# COUNT.net
KiCad netlist of a schematic drawn in EAGLE
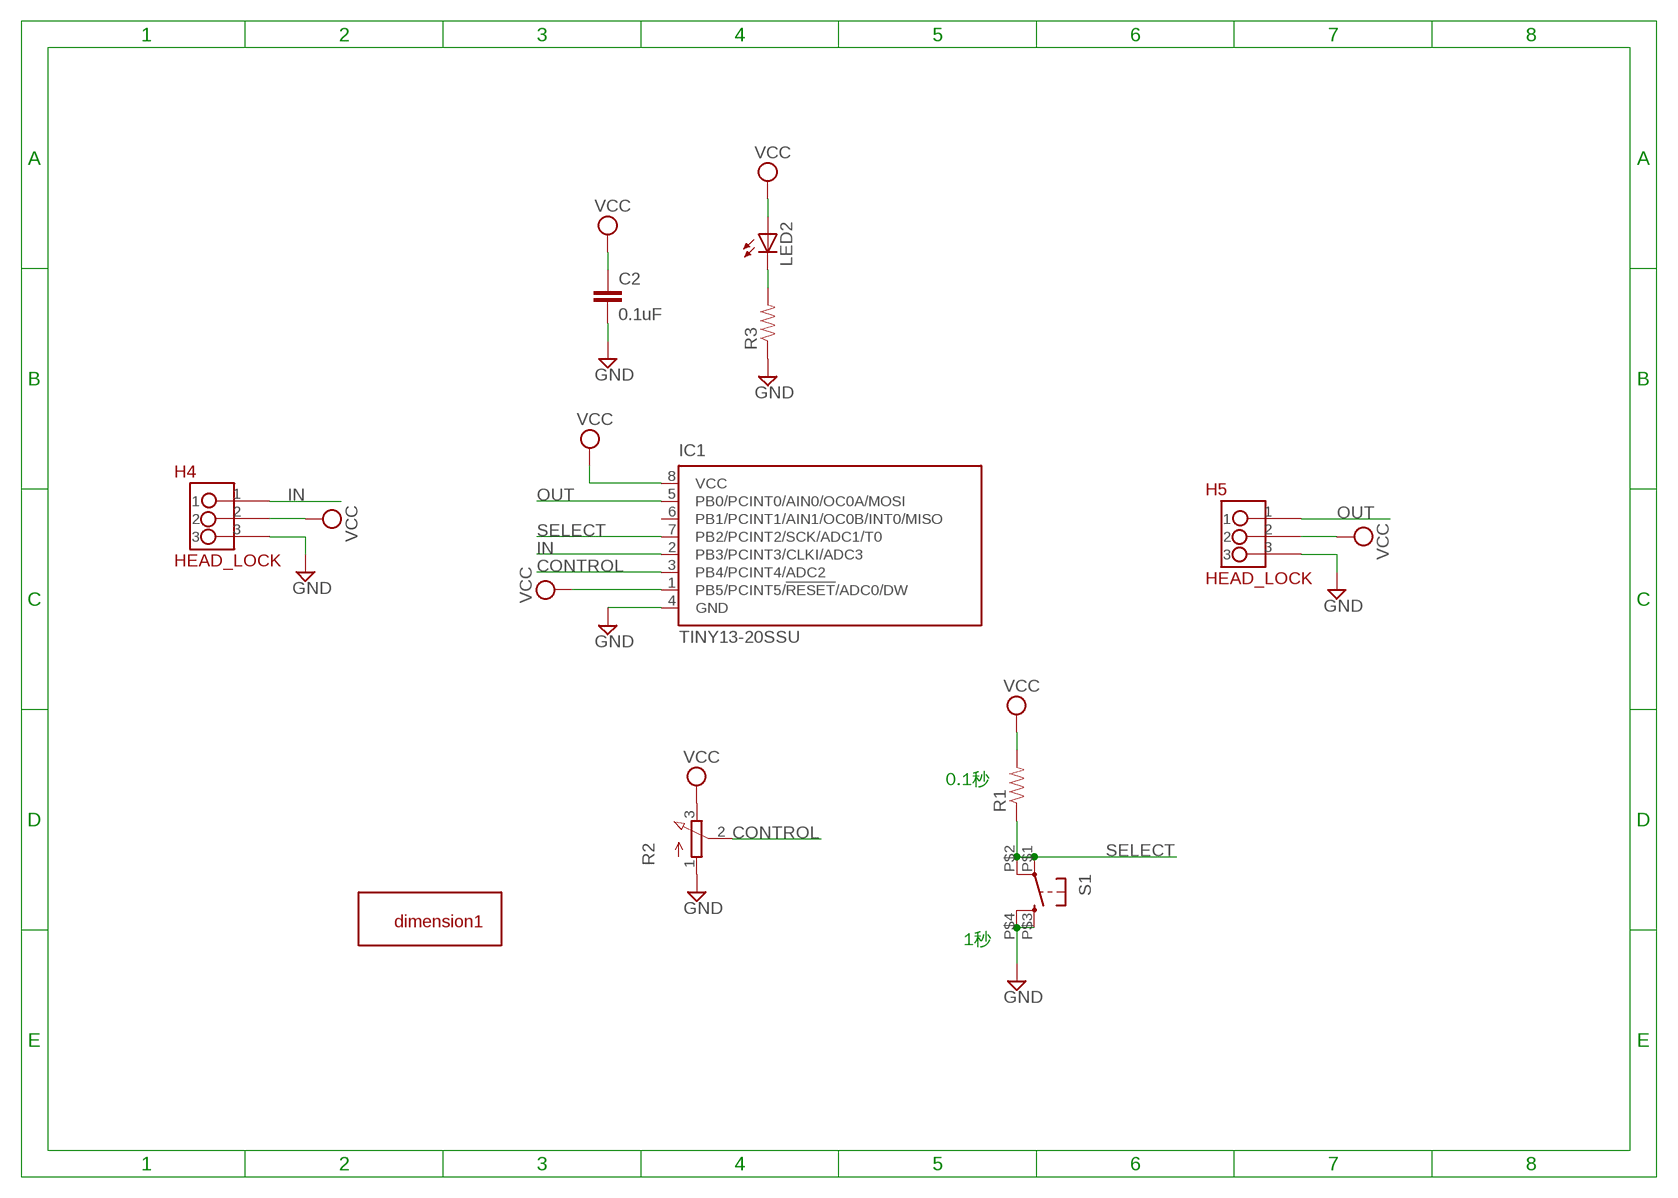
[diagram p0: schematic, sheet 1]

(export (version "E")
  (design (tool "Eeschema 10.0.6"))
  (components
    (comp (ref "C2")
      (value "0.1uF")
      (footprint "eagle-import:0603-CAP")
      (libsource (lib "eagle-import") (part "CAP0603-CAP"))
    )
    (comp (ref "H4")
      (value "HEAD_LOCK")
      (footprint "eagle-import:HEAD_LOCK")
      (libsource (lib "eagle-import") (part "HEAD_LOCK"))
    )
    (comp (ref "H5")
      (value "HEAD_LOCK")
      (footprint "eagle-import:HEAD_LOCK")
      (libsource (lib "eagle-import") (part "HEAD_LOCK"))
    )
    (comp (ref "IC1")
      (value "TINY13-20SSU")
      (footprint "eagle-import:8S1")
      (fields (field (name "MPN") "ATTINY13-20SSU"))
      (libsource (lib "eagle-import") (part "TINY13SSU-20"))
    )
    (comp (ref "LED2")
      (value "LED_ESML0603")
      (footprint "eagle-import:LED_SML0603")
      (libsource (lib "eagle-import") (part "LED_ESML0603"))
    )
    (comp (ref "R1")
      (value "RESISTOR0603-RES")
      (footprint "eagle-import:0603-RES")
      (libsource (lib "eagle-import") (part "RESISTOR0603-RES"))
    )
    (comp (ref "R2")
      (value "3RP/1610N")
      (footprint "eagle-import:3RP_1610N")
      (libsource (lib "eagle-import") (part "3RP/1610N"))
    )
    (comp (ref "R3")
      (value "0.27OHM-1/10W-1%(0603)")
      (footprint "eagle-import:0603-RES")
      (libsource (lib "eagle-import") (part "0.27OHM-1/10W-1%(0603)"))
    )
    (comp (ref "S1")
      (value "TAC_SWITCHKSA_SEALED")
      (footprint "eagle-import:KSA_SEALED_TAC_SWITCH")
      (libsource (lib "eagle-import") (part "TAC_SWITCHKSA_SEALED"))
    )
    (comp (ref "U$1")
      (value "DIMENSION1")
      (footprint "eagle-import:DIMENSION1")
      (libsource (lib "eagle-import") (part "DIMENSION1"))
    )
  )
  (nets
    (net (code "1") (name "/CONTROL") (class "Default")
      (node (ref "IC1") (pin "3") (pinfunction "PB4/PCINT4/ADC2_3") (pintype "bidirectional"))
      (node (ref "R2") (pin "2") (pinfunction "S_2") (pintype "passive"))
    )
    (net (code "2") (name "/IN") (class "Default")
      (node (ref "H4") (pin "1") (pinfunction "1_1") (pintype "passive"))
      (node (ref "IC1") (pin "2") (pinfunction "PB3/PCINT3/CLKI/ADC3_2") (pintype "bidirectional"))
    )
    (net (code "3") (name "/OUT") (class "Default")
      (node (ref "H5") (pin "1") (pinfunction "1_1") (pintype "passive"))
      (node (ref "IC1") (pin "5") (pinfunction "PB0/PCINT0/AIN0/OC0A/MOSI_5") (pintype "bidirectional"))
    )
    (net (code "4") (name "/SELECT") (class "Default")
      (node (ref "IC1") (pin "7") (pinfunction "PB2/PCINT2/SCK/ADC1/T0_7") (pintype "bidirectional"))
      (node (ref "R1") (pin "1") (pinfunction "1_1") (pintype "passive"))
      (node (ref "S1") (pin "P$1") (pinfunction "1_P$1") (pintype "passive"))
      (node (ref "S1") (pin "P$2") (pinfunction "2_P$2") (pintype "passive"))
    )
    (net (code "5") (name "GND") (class "Default")
      (node (ref "C2") (pin "2") (pinfunction "2_2") (pintype "passive"))
      (node (ref "H4") (pin "3") (pinfunction "3_3") (pintype "passive"))
      (node (ref "H5") (pin "3") (pinfunction "3_3") (pintype "passive"))
      (node (ref "IC1") (pin "4") (pinfunction "GND_4") (pintype "power_in"))
      (node (ref "R2") (pin "1") (pinfunction "A_1") (pintype "passive"))
      (node (ref "R3") (pin "1") (pinfunction "1_1") (pintype "passive"))
      (node (ref "S1") (pin "P$3") (pinfunction "3_P$3") (pintype "passive"))
      (node (ref "S1") (pin "P$4") (pinfunction "4_P$4") (pintype "passive"))
    )
    (net (code "6") (name "Net-(LED2-PadC)") (class "Default")
      (node (ref "LED2") (pin "C") (pinfunction "C_C") (pintype "passive"))
      (node (ref "R3") (pin "2") (pinfunction "2_2") (pintype "passive"))
    )
    (net (code "7") (name "VCC") (class "Default")
      (node (ref "C2") (pin "1") (pinfunction "1_1") (pintype "passive"))
      (node (ref "H4") (pin "2") (pinfunction "2_2") (pintype "passive"))
      (node (ref "H5") (pin "2") (pinfunction "2_2") (pintype "passive"))
      (node (ref "IC1") (pin "1") (pinfunction "PB5/PCINT5/~{RESET}/ADC0/DW_1") (pintype "bidirectional"))
      (node (ref "IC1") (pin "8") (pinfunction "VCC_8") (pintype "power_in"))
      (node (ref "LED2") (pin "A") (pinfunction "A_A") (pintype "passive"))
      (node (ref "R1") (pin "2") (pinfunction "2_2") (pintype "passive"))
      (node (ref "R2") (pin "3") (pinfunction "E_3") (pintype "passive"))
    )
    (net (code "8") (name "unconnected-(IC1-PB1{slash}PCINT1{slash}AIN1{slash}OC0B{slash}INT0{slash}MISO-Pad6)") (class "Default")
      (node (ref "IC1") (pin "6") (pinfunction "PB1/PCINT1/AIN1/OC0B/INT0/MISO_6") (pintype "bidirectional"))
    )
  )
)
